# FMB120_jigv3_00.net
KiCad netlist of a schematic drawn in EAGLE
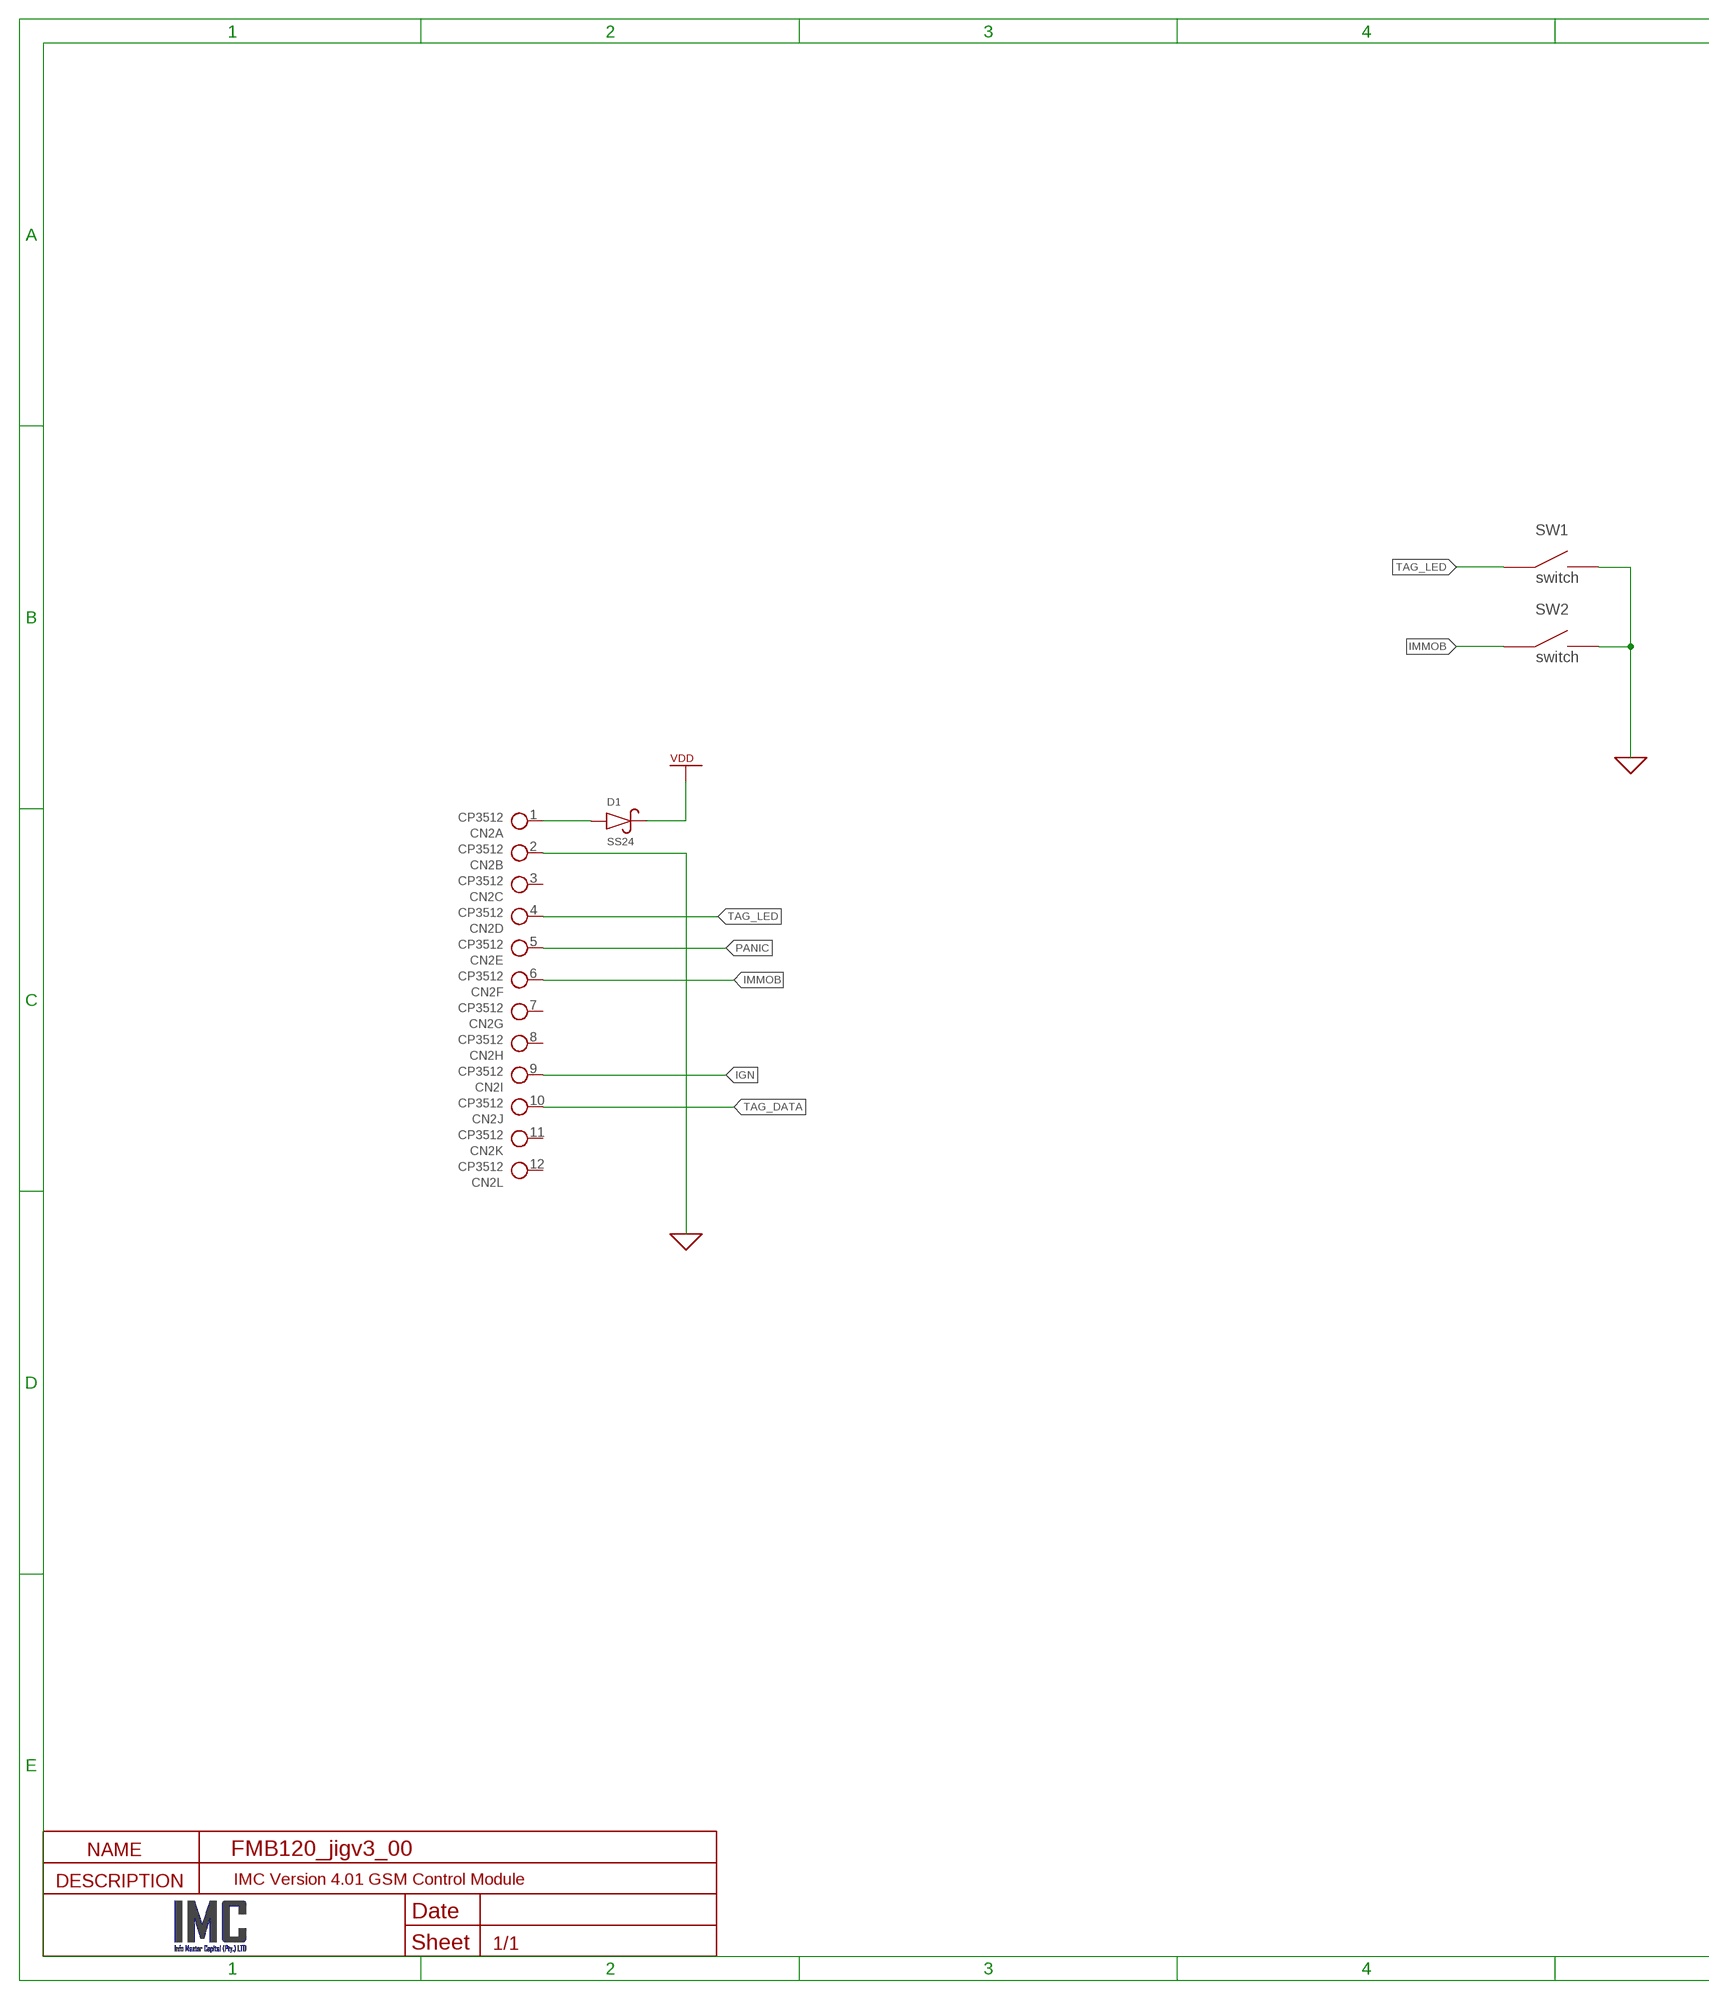
[diagram p0: schematic, sheet 1, part 1 of 2]
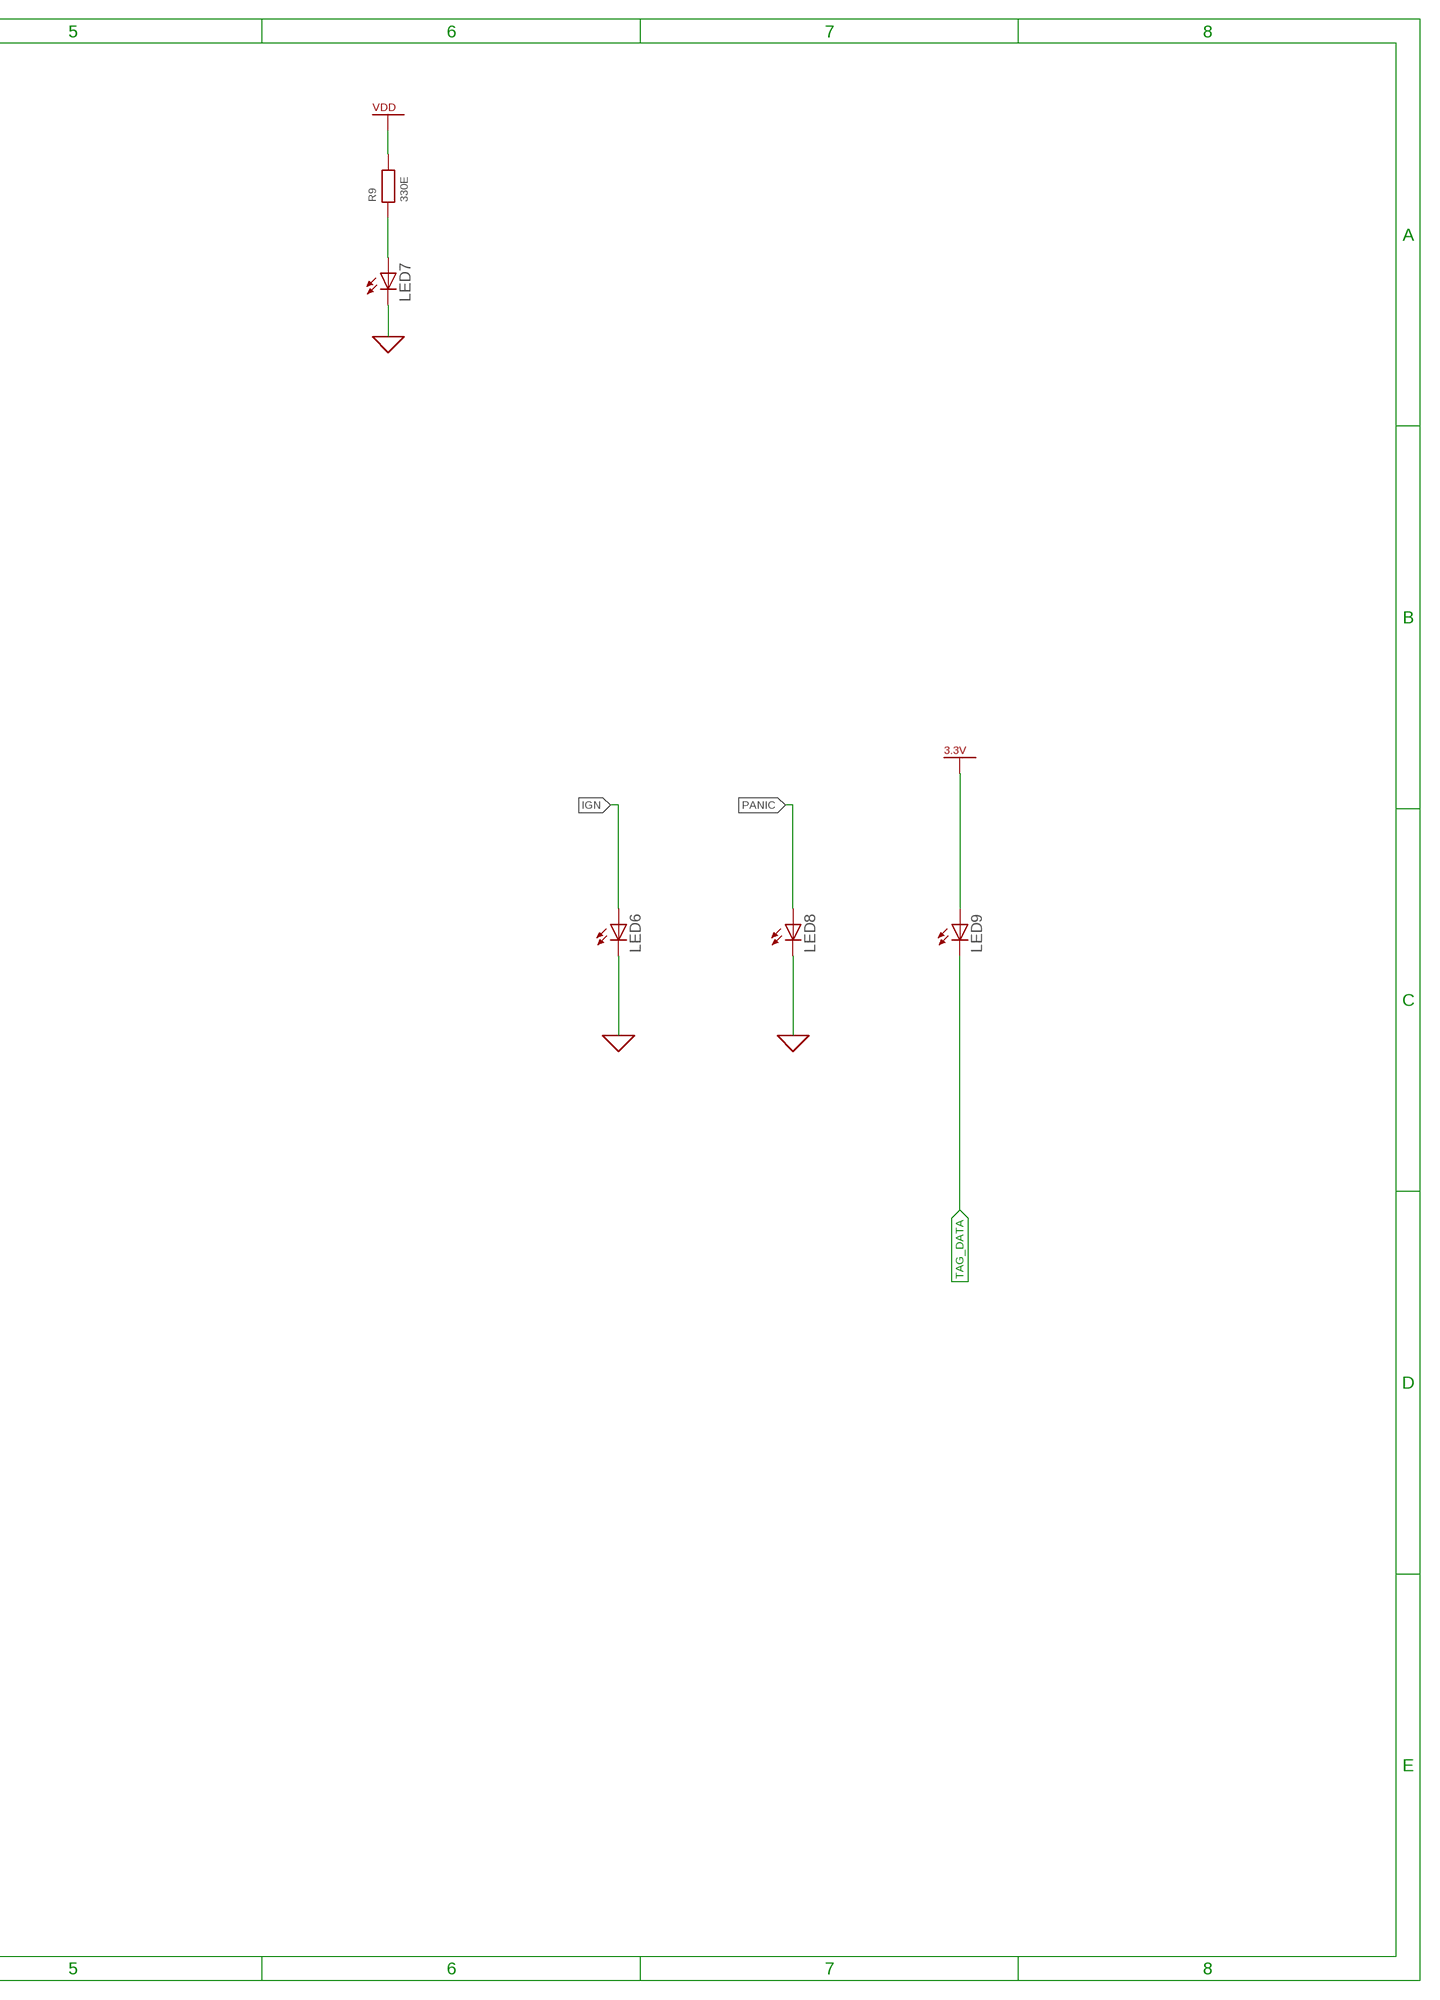
[diagram p1: schematic, sheet 1, part 2 of 2]

(export (version "E")
  (design (tool "Eeschema 10.0.6"))
  (components
    (comp (ref "CN2")
      (value "CP3512")
      (footprint "eagle-import:CP3512_BLU")
      (libsource (lib "eagle-import") (part "12-WAY_THRU_BLU"))
    )
    (comp (ref "D1")
      (value "SS24")
      (footprint "eagle-import:SMB")
      (libsource (lib "eagle-import") (part "DIODE-SHOTKY_SS24"))
    )
    (comp (ref "LED6")
      (value "LED3MM")
      (footprint "eagle-import:LED3MM")
      (libsource (lib "eagle-import") (part "LED3MM"))
    )
    (comp (ref "LED7")
      (value "LED3MM")
      (footprint "eagle-import:LED3MM")
      (libsource (lib "eagle-import") (part "LED3MM"))
    )
    (comp (ref "LED8")
      (value "LED3MM")
      (footprint "eagle-import:LED3MM")
      (libsource (lib "eagle-import") (part "LED3MM"))
    )
    (comp (ref "LED9")
      (value "LED3MM")
      (footprint "eagle-import:LED3MM")
      (libsource (lib "eagle-import") (part "LED3MM"))
    )
    (comp (ref "R9")
      (value "330E")
      (footprint "eagle-import:R0603")
      (libsource (lib "eagle-import") (part "CHIP-RESISTOR_330E"))
    )
    (comp (ref "SW1")
      (value "switch")
      (footprint "eagle-import:SIL_2")
      (libsource (lib "eagle-import") (part "SWITCH_PM"))
    )
    (comp (ref "SW2")
      (value "switch")
      (footprint "eagle-import:SIL_2")
      (libsource (lib "eagle-import") (part "SWITCH_PM"))
    )
  )
  (nets
    (net (code "1") (name "3.3V") (class "Default")
      (node (ref "LED9") (pin "A") (pinfunction "A_A") (pintype "passive"))
    )
    (net (code "2") (name "GND") (class "Default")
      (node (ref "CN2") (pin "2") (pinfunction "P$1_2") (pintype "bidirectional"))
      (node (ref "LED6") (pin "K") (pinfunction "C_K") (pintype "passive"))
      (node (ref "LED7") (pin "K") (pinfunction "C_K") (pintype "passive"))
      (node (ref "LED8") (pin "K") (pinfunction "C_K") (pintype "passive"))
      (node (ref "SW1") (pin "2") (pinfunction "2_2") (pintype "bidirectional"))
      (node (ref "SW2") (pin "2") (pinfunction "2_2") (pintype "bidirectional"))
    )
    (net (code "3") (name "IGN") (class "Default")
      (node (ref "CN2") (pin "9") (pinfunction "P$1_9") (pintype "bidirectional"))
      (node (ref "LED6") (pin "A") (pinfunction "A_A") (pintype "passive"))
    )
    (net (code "4") (name "IMMOB") (class "Default")
      (node (ref "CN2") (pin "6") (pinfunction "P$1_6") (pintype "bidirectional"))
      (node (ref "SW2") (pin "1") (pinfunction "1_1") (pintype "bidirectional"))
    )
    (net (code "5") (name "Net-(CN2A-P$1)") (class "Default")
      (node (ref "CN2") (pin "1") (pinfunction "P$1_1") (pintype "bidirectional"))
      (node (ref "D1") (pin "A") (pinfunction "A_A") (pintype "bidirectional"))
    )
    (net (code "6") (name "Net-(LED7-PadA)") (class "Default")
      (node (ref "LED7") (pin "A") (pinfunction "A_A") (pintype "passive"))
      (node (ref "R9") (pin "1") (pinfunction "1_1") (pintype "bidirectional"))
    )
    (net (code "7") (name "PANIC") (class "Default")
      (node (ref "CN2") (pin "5") (pinfunction "P$1_5") (pintype "bidirectional"))
      (node (ref "LED8") (pin "A") (pinfunction "A_A") (pintype "passive"))
    )
    (net (code "8") (name "TAG_DATA") (class "Default")
      (node (ref "CN2") (pin "10") (pinfunction "P$1_10") (pintype "bidirectional"))
      (node (ref "LED9") (pin "K") (pinfunction "C_K") (pintype "passive"))
    )
    (net (code "9") (name "TAG_LED") (class "Default")
      (node (ref "CN2") (pin "4") (pinfunction "P$1_4") (pintype "bidirectional"))
      (node (ref "SW1") (pin "1") (pinfunction "1_1") (pintype "bidirectional"))
    )
    (net (code "10") (name "VDD") (class "Default")
      (node (ref "D1") (pin "C") (pinfunction "K_C") (pintype "bidirectional"))
      (node (ref "R9") (pin "2") (pinfunction "2_2") (pintype "bidirectional"))
    )
    (net (code "11") (name "unconnected-(CN2C-P$1-Pad3)") (class "Default")
      (node (ref "CN2") (pin "3") (pinfunction "P$1_3") (pintype "bidirectional"))
    )
    (net (code "12") (name "unconnected-(CN2G-P$1-Pad7)") (class "Default")
      (node (ref "CN2") (pin "7") (pinfunction "P$1_7") (pintype "bidirectional"))
    )
    (net (code "13") (name "unconnected-(CN2H-P$1-Pad8)") (class "Default")
      (node (ref "CN2") (pin "8") (pinfunction "P$1_8") (pintype "bidirectional"))
    )
    (net (code "14") (name "unconnected-(CN2K-P$1-Pad11)") (class "Default")
      (node (ref "CN2") (pin "11") (pinfunction "P$1_11") (pintype "bidirectional"))
    )
    (net (code "15") (name "unconnected-(CN2L-P$1-Pad12)") (class "Default")
      (node (ref "CN2") (pin "12") (pinfunction "P$1_12") (pintype "bidirectional"))
    )
  )
)
